# PWM_Signal_Isolation.net
KiCad netlist of a schematic drawn in Altium Designer
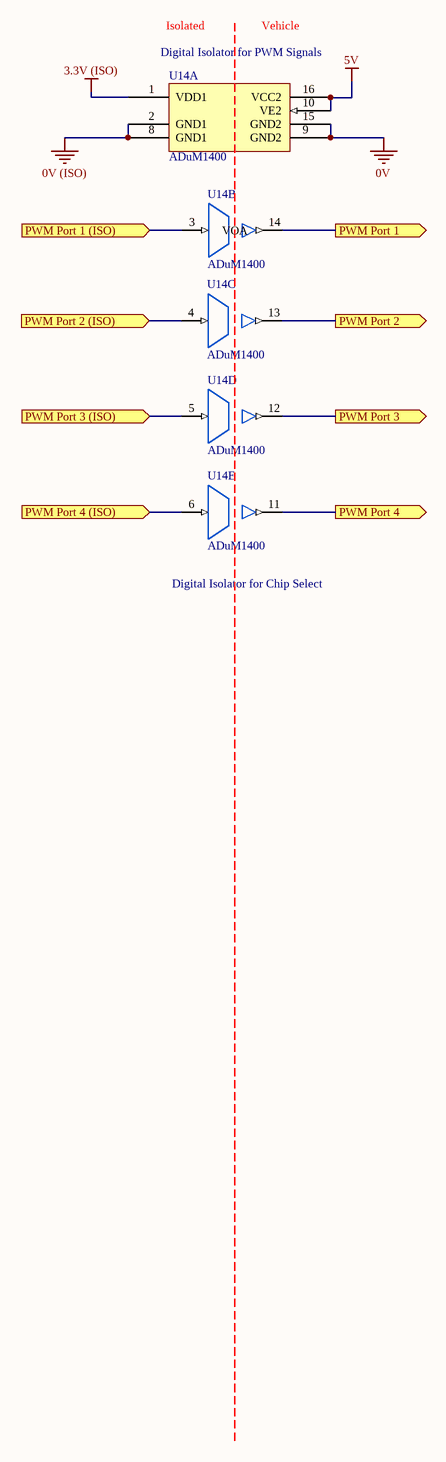
[diagram p0: PWM Signal Isolation.SchDoc]

(export (version "E")
  (design (tool "Eeschema 10.0.6"))
  (components
    (comp (ref "U14")
      (value "ADuM1400")
      (footprint "AD 16-SOIC")
      (fields
        (field (name "MANUFACTURER") "Analog Devices")
        (field (name "DIGIKEY PART NUMBER") "ADUM1400WSRWZ-ND")
      )
      (libsource (lib "ts_standard_library") (part "ADuM1400"))
    )
  )
  (nets
    (net (code "1") (name "/PWM Port 1") (class "Default")
      (node (ref "U14") (pin "14") (pinfunction "VOA_14") (pintype "output"))
    )
    (net (code "2") (name "/PWM Port 1 (ISO)") (class "Default")
      (node (ref "U14") (pin "3") (pinfunction "VIA_3") (pintype "input"))
    )
    (net (code "3") (name "/PWM Port 2") (class "Default")
      (node (ref "U14") (pin "13") (pinfunction "VOB_13") (pintype "output"))
    )
    (net (code "4") (name "/PWM Port 2 (ISO)") (class "Default")
      (node (ref "U14") (pin "4") (pinfunction "VIB_4") (pintype "input"))
    )
    (net (code "5") (name "/PWM Port 3") (class "Default")
      (node (ref "U14") (pin "12") (pinfunction "VOC_12") (pintype "output"))
    )
    (net (code "6") (name "/PWM Port 3 (ISO)") (class "Default")
      (node (ref "U14") (pin "5") (pinfunction "VIC_5") (pintype "input"))
    )
    (net (code "7") (name "/PWM Port 4") (class "Default")
      (node (ref "U14") (pin "11") (pinfunction "VOD_11") (pintype "output"))
    )
    (net (code "8") (name "/PWM Port 4 (ISO)") (class "Default")
      (node (ref "U14") (pin "6") (pinfunction "VID_6") (pintype "input"))
    )
    (net (code "9") (name "0V") (class "Default")
      (node (ref "U14") (pin "15") (pinfunction "GND2_15") (pintype "power_in"))
      (node (ref "U14") (pin "9") (pinfunction "GND2_9") (pintype "power_in"))
    )
    (net (code "10") (name "0V (ISO)") (class "Default")
      (node (ref "U14") (pin "2") (pinfunction "GND1_2") (pintype "power_in"))
      (node (ref "U14") (pin "8") (pinfunction "GND1_8") (pintype "power_in"))
    )
    (net (code "11") (name "3.3V (ISO)") (class "Default")
      (node (ref "U14") (pin "1") (pinfunction "VDD1_1") (pintype "power_in"))
    )
    (net (code "12") (name "5V") (class "Default")
      (node (ref "U14") (pin "10") (pinfunction "VE2_10") (pintype "input"))
      (node (ref "U14") (pin "16") (pinfunction "VCC2_16") (pintype "power_in"))
    )
  )
)
